# upgrade.net
KiCad netlist of a schematic drawn in Altium Designer
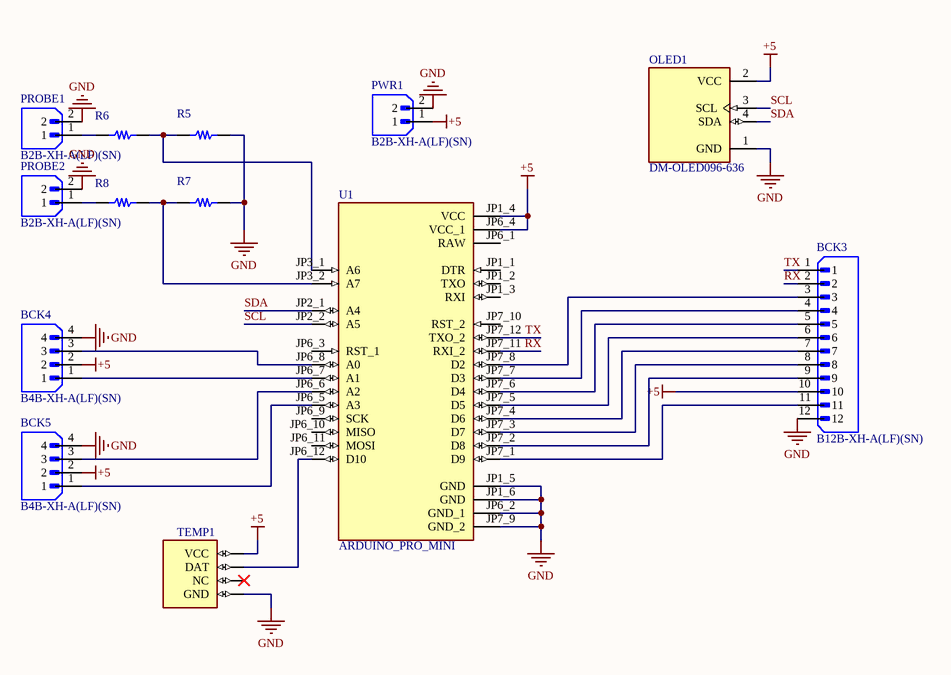
[diagram p0: upgrade.SchDoc]

(export (version "E")
  (design (tool "Eeschema 10.0.6"))
  (components
    (comp (ref "BCK3")
      (value "B12B-XH-A(LF)(SN)")
      (footprint "JST_B12B-XH-A(LF)(SN)")
      (description "Connector Header Through Hole 12 position 0.098 (2.50mm)")
      (fields (field (name "MF") "JST Sales"))
      (libsource (lib "CSD Robocon Workspace") (part "B12B-XH-A(LF)(SN)"))
    )
    (comp (ref "BCK4")
      (value "B4B-XH-A(LF)(SN)")
      (footprint "JST_B4B-XH-A(LF)(SN)")
      (description "Connector Header Through Hole 4 position 0.098 (2.50mm)")
      (fields (field (name "MF") "JST Sales"))
      (libsource (lib "CSD Robocon Workspace") (part "B4B-XH-A(LF)(SN)"))
    )
    (comp (ref "BCK5")
      (value "B4B-XH-A(LF)(SN)")
      (footprint "JST_B4B-XH-A(LF)(SN)")
      (description "Connector Header Through Hole 4 position 0.098 (2.50mm)")
      (fields (field (name "MF") "JST Sales"))
      (libsource (lib "CSD Robocon Workspace") (part "B4B-XH-A(LF)(SN)"))
    )
    (comp (ref "OLED1")
      (value "DM-OLED096-636")
      (footprint "MODULE_DM-OLED096-636")
      (description "128 X 64 Monochrome Graphic OLED Display Module")
      (fields (field (name "MF") "Display Module"))
      (libsource (lib "CSD Robocon Workspace") (part "DM-OLED096-636"))
    )
    (comp (ref "PROBE1")
      (value "B2B-XH-A(LF)(SN)")
      (footprint "JST_B2B-XH-A(LF)(SN)")
      (description "Connector Header Through Hole 2 position 0.098 (2.50mm)")
      (fields (field (name "MF") "JST Sales America Inc."))
      (libsource (lib "CSD Robocon Workspace") (part "B2B-XH-A(LF)(SN)"))
    )
    (comp (ref "PROBE2")
      (value "B2B-XH-A(LF)(SN)")
      (footprint "JST_B2B-XH-A(LF)(SN)")
      (description "Connector Header Through Hole 2 position 0.098 (2.50mm)")
      (fields (field (name "MF") "JST Sales America Inc."))
      (libsource (lib "CSD Robocon Workspace") (part "B2B-XH-A(LF)(SN)"))
    )
    (comp (ref "PWR1")
      (value "B2B-XH-A(LF)(SN)")
      (footprint "JST_B2B-XH-A(LF)(SN)")
      (description "Connector Header Through Hole 2 position 0.098 (2.50mm)")
      (fields (field (name "MF") "JST Sales America Inc."))
      (libsource (lib "CSD Robocon Workspace") (part "B2B-XH-A(LF)(SN)"))
    )
    (comp (ref "R5")
      (value "generic_res")
      (footprint "generic_res_footprint")
      (description "Generic through hole resistor")
      (libsource (lib "CSD Robocon Workspace") (part "generic_res"))
    )
    (comp (ref "R6")
      (value "generic_res")
      (footprint "generic_res_footprint")
      (description "Generic through hole resistor")
      (libsource (lib "CSD Robocon Workspace") (part "generic_res"))
    )
    (comp (ref "R7")
      (value "generic_res")
      (footprint "generic_res_footprint")
      (description "Generic through hole resistor")
      (libsource (lib "CSD Robocon Workspace") (part "generic_res"))
    )
    (comp (ref "R8")
      (value "generic_res")
      (footprint "generic_res_footprint")
      (description "Generic through hole resistor")
      (libsource (lib "CSD Robocon Workspace") (part "generic_res"))
    )
    (comp (ref "TEMP1")
      (value "dht11_symbol")
      (footprint "dht11_footprint")
      (description "Humidity, Temperature Digital Â±5% RH Through Hole")
      (fields (field (name "MF") "UNIVERSAL-SOLDER Electronics Ltd") (field (name "MP") "DHT11"))
      (libsource (lib "CSD Robocon Workspace") (part "dht11_symbol"))
    )
    (comp (ref "U1")
      (value "ARDUINO_PRO_MINI")
      (footprint "MODULE_ARDUINO_PRO_MINI")
      (fields (field (name "MP") "Arduino Pro Mini") (field (name "MF") "Arduino"))
      (libsource (lib "CSD Robocon Workspace") (part "ARDUINO_PRO_MINI"))
    )
  )
  (nets
    (net (code "1") (name "+5") (class "Default")
      (node (ref "BCK3") (pin "10") (pinfunction "10_10") (pintype "passive"))
      (node (ref "BCK4") (pin "2") (pinfunction "2_2") (pintype "passive"))
      (node (ref "BCK5") (pin "2") (pinfunction "2_2") (pintype "passive"))
      (node (ref "OLED1") (pin "2") (pinfunction "VCC_2") (pintype "power_in"))
      (node (ref "PWR1") (pin "1") (pinfunction "1_1") (pintype "passive"))
      (node (ref "TEMP1") (pin "1") (pinfunction "VCC_1") (pintype "bidirectional"))
      (node (ref "U1") (pin "JP1_4") (pinfunction "VCC_JP1_4") (pintype "power_in"))
      (node (ref "U1") (pin "JP6_4") (pinfunction "VCC_1_JP6_4") (pintype "power_in"))
    )
    (net (code "2") (name "/RX") (class "Default")
      (node (ref "BCK3") (pin "2") (pinfunction "2_2") (pintype "passive"))
      (node (ref "U1") (pin "JP7_11") (pinfunction "RXI_2_JP7_11") (pintype "bidirectional"))
    )
    (net (code "3") (name "/SCL") (class "Default")
      (node (ref "OLED1") (pin "3") (pinfunction "SCL_3") (pintype "input"))
      (node (ref "U1") (pin "JP2_2") (pinfunction "A5_JP2_2") (pintype "bidirectional"))
    )
    (net (code "4") (name "/SDA") (class "Default")
      (node (ref "OLED1") (pin "4") (pinfunction "SDA_4") (pintype "bidirectional"))
      (node (ref "U1") (pin "JP2_1") (pinfunction "A4_JP2_1") (pintype "bidirectional"))
    )
    (net (code "5") (name "/TX") (class "Default")
      (node (ref "BCK3") (pin "1") (pinfunction "1_1") (pintype "passive"))
      (node (ref "U1") (pin "JP7_12") (pinfunction "TXO_2_JP7_12") (pintype "bidirectional"))
    )
    (net (code "6") (name "GND") (class "Default")
      (node (ref "BCK3") (pin "12") (pinfunction "12_12") (pintype "passive"))
      (node (ref "BCK4") (pin "4") (pinfunction "4_4") (pintype "passive"))
      (node (ref "BCK5") (pin "4") (pinfunction "4_4") (pintype "passive"))
      (node (ref "OLED1") (pin "1") (pinfunction "GND_1") (pintype "power_in"))
      (node (ref "PROBE1") (pin "2") (pinfunction "2_2") (pintype "passive"))
      (node (ref "PROBE2") (pin "2") (pinfunction "2_2") (pintype "passive"))
      (node (ref "PWR1") (pin "2") (pinfunction "2_2") (pintype "passive"))
      (node (ref "R5") (pin "1") (pinfunction "1_1") (pintype "passive"))
      (node (ref "R7") (pin "1") (pinfunction "1_1") (pintype "passive"))
      (node (ref "TEMP1") (pin "4") (pinfunction "GND_4") (pintype "bidirectional"))
      (node (ref "U1") (pin "JP1_5") (pinfunction "GND_JP1_5") (pintype "power_in"))
      (node (ref "U1") (pin "JP1_6") (pinfunction "GND_JP1_6") (pintype "power_in"))
      (node (ref "U1") (pin "JP6_2") (pinfunction "GND_1_JP6_2") (pintype "power_in"))
      (node (ref "U1") (pin "JP7_9") (pinfunction "GND_2_JP7_9") (pintype "power_in"))
    )
    (net (code "7") (name "Net-(PROBE1-Pad1)") (class "Default")
      (node (ref "PROBE1") (pin "1") (pinfunction "1_1") (pintype "passive"))
      (node (ref "R6") (pin "2") (pinfunction "2_2") (pintype "passive"))
    )
    (net (code "8") (name "Net-(PROBE2-Pad1)") (class "Default")
      (node (ref "PROBE2") (pin "1") (pinfunction "1_1") (pintype "passive"))
      (node (ref "R8") (pin "2") (pinfunction "2_2") (pintype "passive"))
    )
    (net (code "9") (name "Net-(TEMP1-DAT)") (class "Default")
      (node (ref "TEMP1") (pin "2") (pinfunction "DAT_2") (pintype "bidirectional"))
      (node (ref "U1") (pin "JP6_12") (pinfunction "D10_JP6_12") (pintype "bidirectional"))
    )
    (net (code "10") (name "Net-(U1-A0)") (class "Default")
      (node (ref "BCK4") (pin "3") (pinfunction "3_3") (pintype "passive"))
      (node (ref "U1") (pin "JP6_8") (pinfunction "A0_JP6_8") (pintype "bidirectional"))
    )
    (net (code "11") (name "Net-(U1-A1)") (class "Default")
      (node (ref "BCK4") (pin "1") (pinfunction "1_1") (pintype "passive"))
      (node (ref "U1") (pin "JP6_7") (pinfunction "A1_JP6_7") (pintype "bidirectional"))
    )
    (net (code "12") (name "Net-(U1-A2)") (class "Default")
      (node (ref "BCK5") (pin "3") (pinfunction "3_3") (pintype "passive"))
      (node (ref "U1") (pin "JP6_6") (pinfunction "A2_JP6_6") (pintype "bidirectional"))
    )
    (net (code "13") (name "Net-(U1-A3)") (class "Default")
      (node (ref "BCK5") (pin "1") (pinfunction "1_1") (pintype "passive"))
      (node (ref "U1") (pin "JP6_5") (pinfunction "A3_JP6_5") (pintype "bidirectional"))
    )
    (net (code "14") (name "Net-(U1-A6)") (class "Default")
      (node (ref "R5") (pin "2") (pinfunction "2_2") (pintype "passive"))
      (node (ref "R6") (pin "1") (pinfunction "1_1") (pintype "passive"))
      (node (ref "U1") (pin "JP3_1") (pinfunction "A6_JP3_1") (pintype "input"))
    )
    (net (code "15") (name "Net-(U1-A7)") (class "Default")
      (node (ref "R7") (pin "2") (pinfunction "2_2") (pintype "passive"))
      (node (ref "R8") (pin "1") (pinfunction "1_1") (pintype "passive"))
      (node (ref "U1") (pin "JP3_2") (pinfunction "A7_JP3_2") (pintype "input"))
    )
    (net (code "16") (name "Net-(U1-D2)") (class "Default")
      (node (ref "BCK3") (pin "3") (pinfunction "3_3") (pintype "passive"))
      (node (ref "U1") (pin "JP7_8") (pinfunction "D2_JP7_8") (pintype "bidirectional"))
    )
    (net (code "17") (name "Net-(U1-D3)") (class "Default")
      (node (ref "BCK3") (pin "4") (pinfunction "4_4") (pintype "passive"))
      (node (ref "U1") (pin "JP7_7") (pinfunction "D3_JP7_7") (pintype "bidirectional"))
    )
    (net (code "18") (name "Net-(U1-D4)") (class "Default")
      (node (ref "BCK3") (pin "5") (pinfunction "5_5") (pintype "passive"))
      (node (ref "U1") (pin "JP7_6") (pinfunction "D4_JP7_6") (pintype "bidirectional"))
    )
    (net (code "19") (name "Net-(U1-D5)") (class "Default")
      (node (ref "BCK3") (pin "6") (pinfunction "6_6") (pintype "passive"))
      (node (ref "U1") (pin "JP7_5") (pinfunction "D5_JP7_5") (pintype "bidirectional"))
    )
    (net (code "20") (name "Net-(U1-D6)") (class "Default")
      (node (ref "BCK3") (pin "7") (pinfunction "7_7") (pintype "passive"))
      (node (ref "U1") (pin "JP7_4") (pinfunction "D6_JP7_4") (pintype "bidirectional"))
    )
    (net (code "21") (name "Net-(U1-D7)") (class "Default")
      (node (ref "BCK3") (pin "8") (pinfunction "8_8") (pintype "passive"))
      (node (ref "U1") (pin "JP7_3") (pinfunction "D7_JP7_3") (pintype "bidirectional"))
    )
    (net (code "22") (name "Net-(U1-D8)") (class "Default")
      (node (ref "BCK3") (pin "9") (pinfunction "9_9") (pintype "passive"))
      (node (ref "U1") (pin "JP7_2") (pinfunction "D8_JP7_2") (pintype "bidirectional"))
    )
    (net (code "23") (name "Net-(U1-D9)") (class "Default")
      (node (ref "BCK3") (pin "11") (pinfunction "11_11") (pintype "passive"))
      (node (ref "U1") (pin "JP7_1") (pinfunction "D9_JP7_1") (pintype "bidirectional"))
    )
    (net (code "24") (name "unconnected-(TEMP1-NC-Pad3)") (class "Default")
      (node (ref "TEMP1") (pin "3") (pinfunction "NC_3") (pintype "bidirectional+no_connect"))
    )
    (net (code "25") (name "unconnected-(U1-DTR-PadJP1_1)") (class "Default")
      (node (ref "U1") (pin "JP1_1") (pinfunction "DTR_JP1_1") (pintype "input"))
    )
    (net (code "26") (name "unconnected-(U1-MISO-PadJP6_10)") (class "Default")
      (node (ref "U1") (pin "JP6_10") (pinfunction "MISO_JP6_10") (pintype "bidirectional"))
    )
    (net (code "27") (name "unconnected-(U1-MOSI-PadJP6_11)") (class "Default")
      (node (ref "U1") (pin "JP6_11") (pinfunction "MOSI_JP6_11") (pintype "bidirectional"))
    )
    (net (code "28") (name "unconnected-(U1-RAW-PadJP6_1)") (class "Default")
      (node (ref "U1") (pin "JP6_1") (pinfunction "RAW_JP6_1") (pintype "power_in"))
    )
    (net (code "29") (name "unconnected-(U1-RST_1-PadJP6_3)") (class "Default")
      (node (ref "U1") (pin "JP6_3") (pinfunction "RST_1_JP6_3") (pintype "input"))
    )
    (net (code "30") (name "unconnected-(U1-RST_2-PadJP7_10)") (class "Default")
      (node (ref "U1") (pin "JP7_10") (pinfunction "RST_2_JP7_10") (pintype "input"))
    )
    (net (code "31") (name "unconnected-(U1-RXI-PadJP1_3)") (class "Default")
      (node (ref "U1") (pin "JP1_3") (pinfunction "RXI_JP1_3") (pintype "bidirectional"))
    )
    (net (code "32") (name "unconnected-(U1-SCK-PadJP6_9)") (class "Default")
      (node (ref "U1") (pin "JP6_9") (pinfunction "SCK_JP6_9") (pintype "bidirectional"))
    )
    (net (code "33") (name "unconnected-(U1-TXO-PadJP1_2)") (class "Default")
      (node (ref "U1") (pin "JP1_2") (pinfunction "TXO_JP1_2") (pintype "bidirectional"))
    )
  )
)
